# harp_rfid_reader.net
KiCad netlist of a schematic drawn in EAGLE
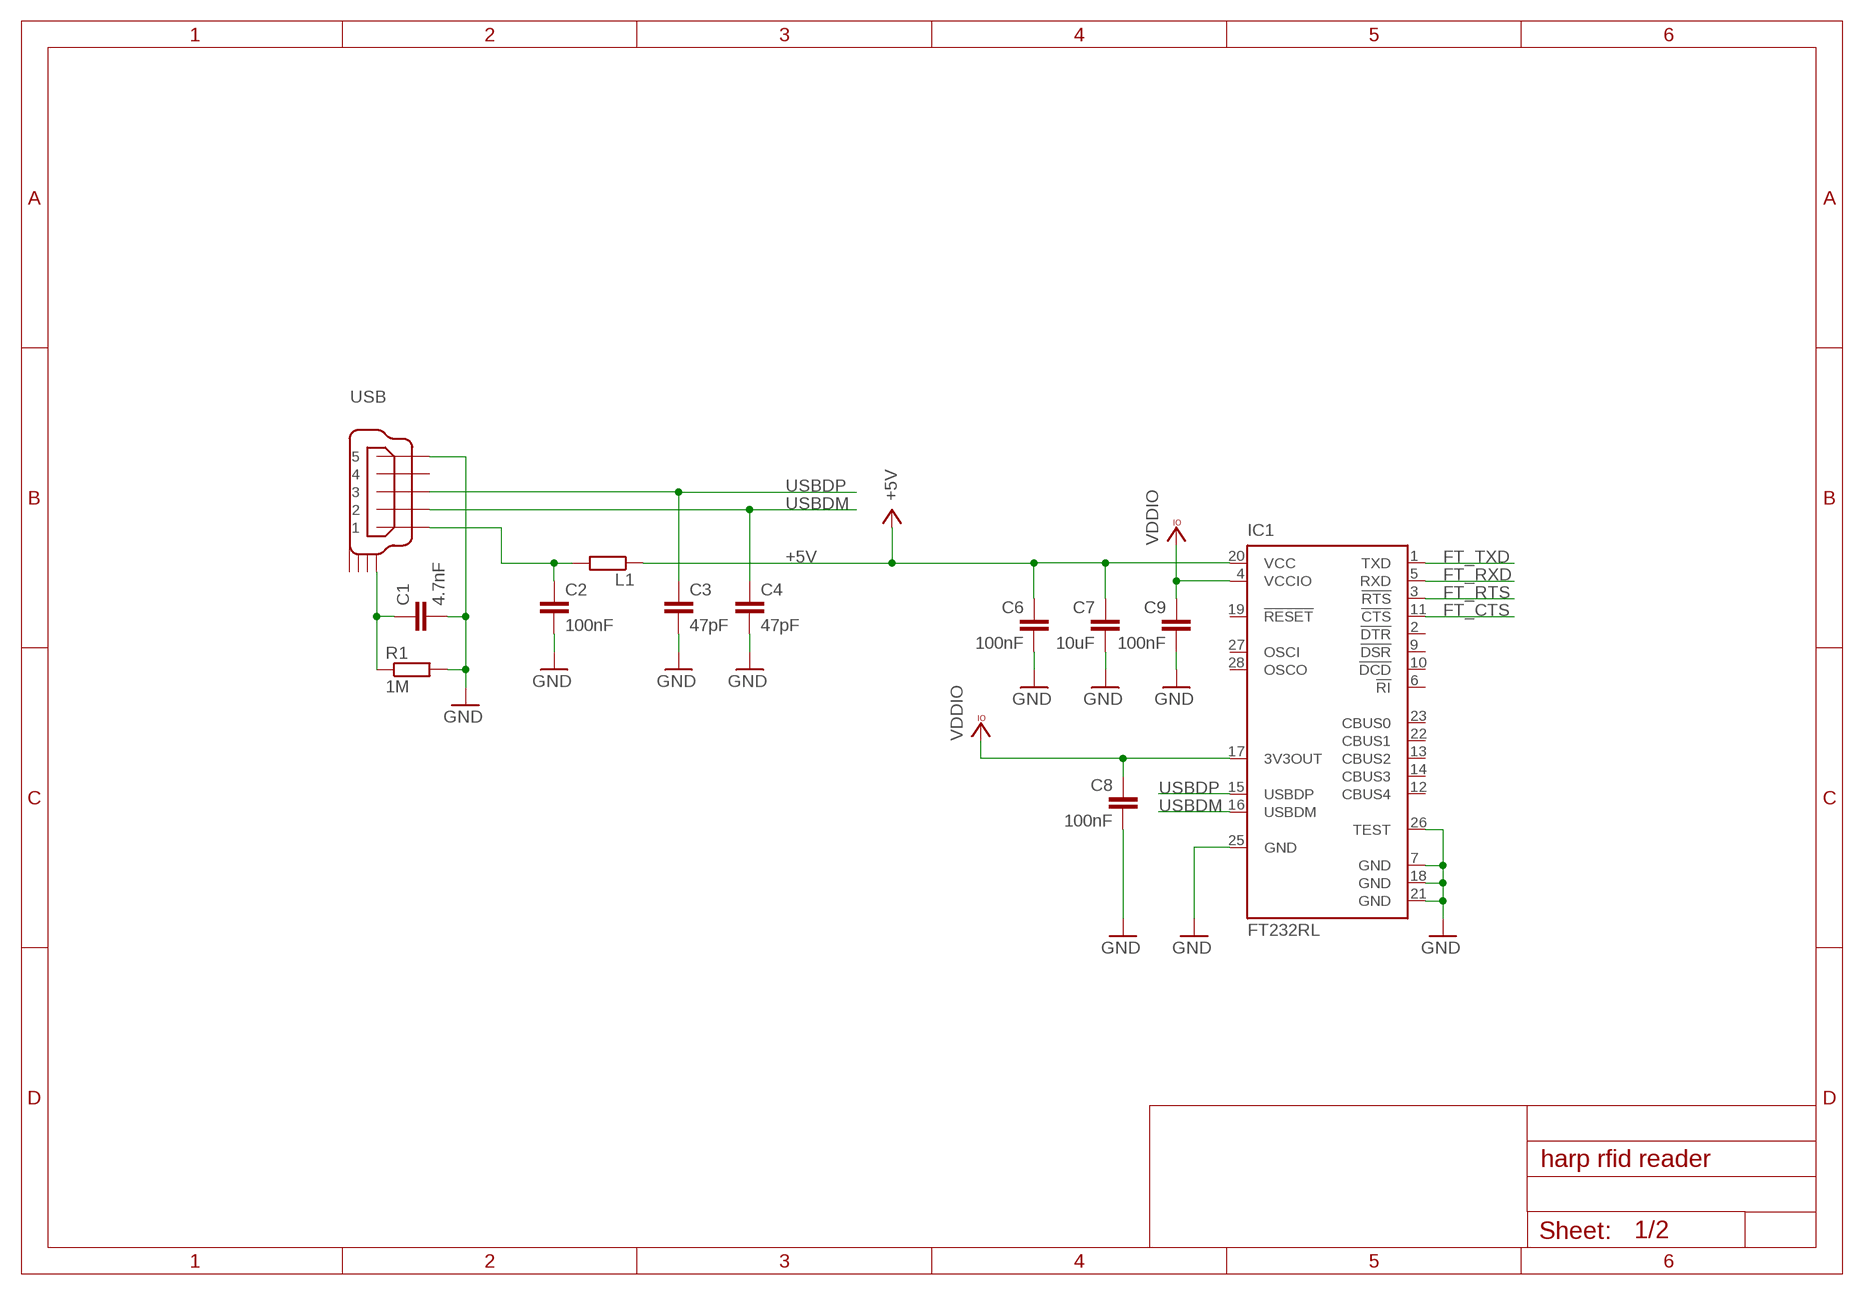
[diagram p0: schematic, sheet 1]
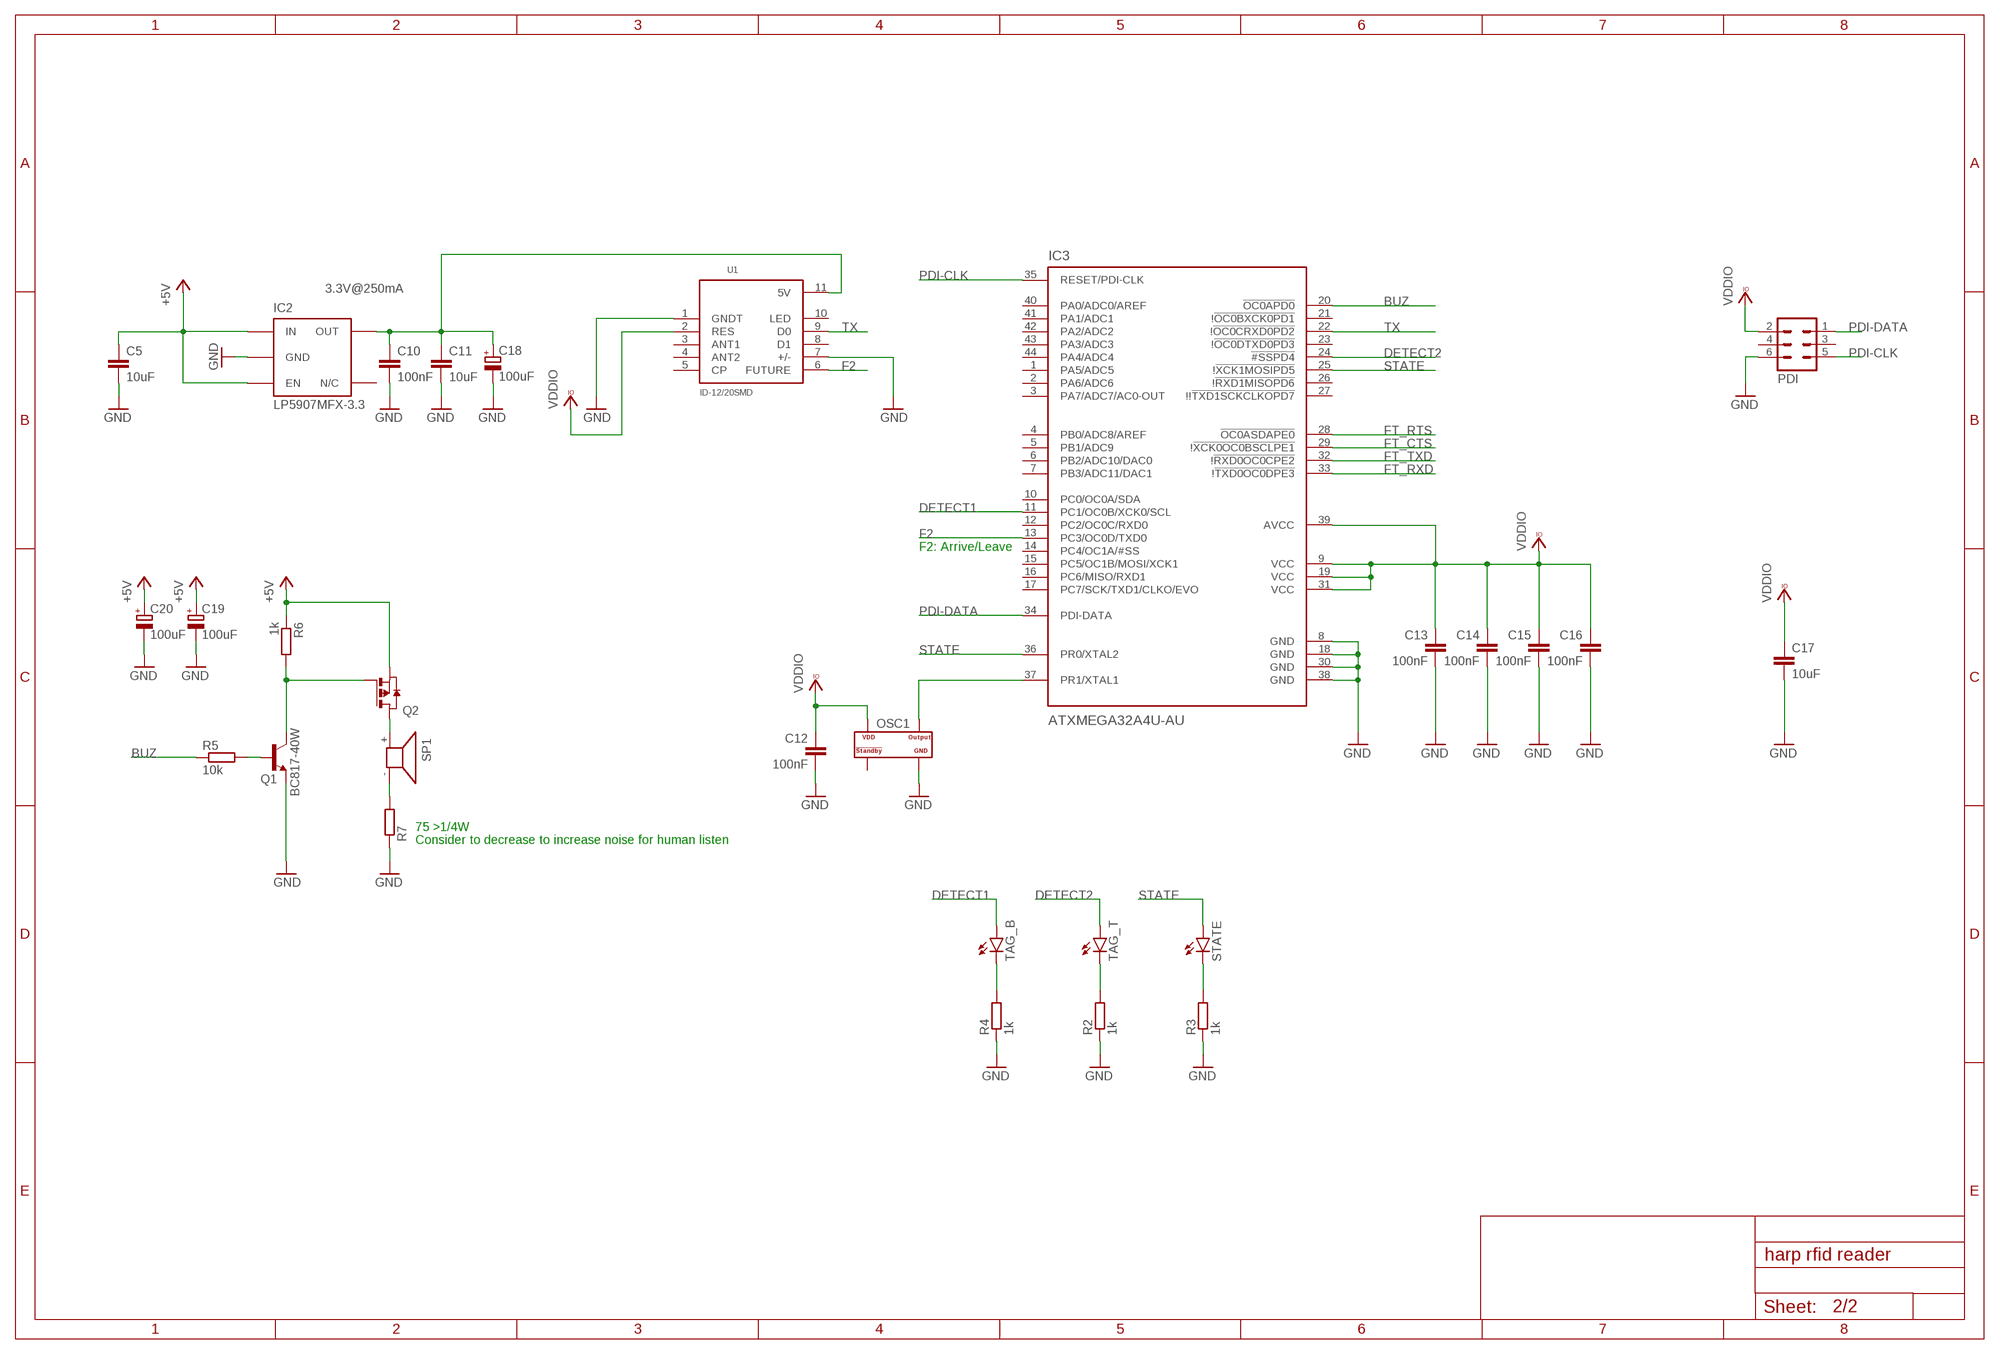
[diagram p1: schematic, sheet 2]

(export (version "E")
  (design (tool "Eeschema 10.0.6"))
  (components
    (comp (ref "C1")
      (value "4.7nF")
      (footprint "eagle-import:C0402")
      (libsource (lib "eagle-import") (part "C-EUC0402"))
    )
    (comp (ref "C2")
      (value "100nF")
      (footprint "eagle-import:C0402")
      (libsource (lib "eagle-import") (part "C-EUC0402"))
    )
    (comp (ref "C3")
      (value "47pF")
      (footprint "eagle-import:C0402")
      (libsource (lib "eagle-import") (part "C-EUC0402"))
    )
    (comp (ref "C4")
      (value "47pF")
      (footprint "eagle-import:C0402")
      (libsource (lib "eagle-import") (part "C-EUC0402"))
    )
    (comp (ref "C6")
      (value "100nF")
      (footprint "eagle-import:C0402")
      (libsource (lib "eagle-import") (part "C-EUC0402"))
    )
    (comp (ref "C7")
      (value "10uF")
      (footprint "eagle-import:C0603")
      (libsource (lib "eagle-import") (part "C-EUC0603"))
    )
    (comp (ref "C8")
      (value "100nF")
      (footprint "eagle-import:C0402")
      (libsource (lib "eagle-import") (part "C-EUC0402"))
    )
    (comp (ref "C9")
      (value "100nF")
      (footprint "eagle-import:C0402")
      (libsource (lib "eagle-import") (part "C-EUC0402"))
    )
    (comp (ref "IC1")
      (value "FT232RL")
      (footprint "eagle-import:SSOP28")
      (libsource (lib "eagle-import") (part "FT232RL"))
    )
    (comp (ref "L1")
      (value "???")
      (footprint "eagle-import:R0805")
      (libsource (lib "eagle-import") (part "R-EU_R0805"))
    )
    (comp (ref "R1")
      (value "1M")
      (footprint "eagle-import:R0402")
      (libsource (lib "eagle-import") (part "R-EU_R0402"))
    )
    (comp (ref "USB")
      (value "USB_MINI_B")
      (footprint "eagle-import:240-0002-1")
      (libsource (lib "eagle-import") (part "USB_MINI_B"))
    )
    (comp (ref "C5")
      (value "10uF")
      (footprint "eagle-import:C0603")
      (libsource (lib "eagle-import") (part "C-EUC0603"))
    )
    (comp (ref "C10")
      (value "100nF")
      (footprint "eagle-import:C0402")
      (libsource (lib "eagle-import") (part "C-EUC0402"))
    )
    (comp (ref "C11")
      (value "10uF")
      (footprint "eagle-import:C0603")
      (libsource (lib "eagle-import") (part "C-EUC0603"))
    )
    (comp (ref "C12")
      (value "100nF")
      (footprint "eagle-import:C0402")
      (libsource (lib "eagle-import") (part "C-EUC0402"))
    )
    (comp (ref "C13")
      (value "100nF")
      (footprint "eagle-import:C0402")
      (libsource (lib "eagle-import") (part "C-EUC0402"))
    )
    (comp (ref "C14")
      (value "100nF")
      (footprint "eagle-import:C0402")
      (libsource (lib "eagle-import") (part "C-EUC0402"))
    )
    (comp (ref "C15")
      (value "100nF")
      (footprint "eagle-import:C0402")
      (libsource (lib "eagle-import") (part "C-EUC0402"))
    )
    (comp (ref "C16")
      (value "100nF")
      (footprint "eagle-import:C0402")
      (libsource (lib "eagle-import") (part "C-EUC0402"))
    )
    (comp (ref "C17")
      (value "10uF")
      (footprint "eagle-import:C0603")
      (libsource (lib "eagle-import") (part "C-EUC0603"))
    )
    (comp (ref "C18")
      (value "100uF")
      (footprint "eagle-import:CT3216")
      (libsource (lib "eagle-import") (part "CPOL-EUCT3216"))
    )
    (comp (ref "C19")
      (value "100uF")
      (footprint "eagle-import:CT3216")
      (libsource (lib "eagle-import") (part "CPOL-EUCT3216"))
    )
    (comp (ref "C20")
      (value "100uF")
      (footprint "eagle-import:CT3216")
      (libsource (lib "eagle-import") (part "CPOL-EUCT3216"))
    )
    (comp (ref "IC2")
      (value "LP5907MFX-3.3")
      (footprint "eagle-import:TSOT23-5")
      (libsource (lib "eagle-import") (part "TLV700XX"))
    )
    (comp (ref "IC3")
      (value "ATXMEGA32A4U-AU")
      (footprint "eagle-import:QFP80P1200X1200X120-44N")
      (libsource (lib "eagle-import") (part "AT-XMEGA-XXA4-AU"))
    )
    (comp (ref "OSC1")
      (value "CNP-MISCELLANEOUS_OSCILLATOR")
      (footprint "eagle-import:CNP-MISCELLANEOUS_OSCILLATOR_3.2X2.5")
      (libsource (lib "eagle-import") (part "CNP-MISCELLANEOUS_OSCILLATOR"))
    )
    (comp (ref "PDI")
      (value "MA03-2")
      (footprint "eagle-import:MA03-2")
      (libsource (lib "eagle-import") (part "MA03-2"))
    )
    (comp (ref "Q1")
      (value "BC817-40W")
      (footprint "eagle-import:SOT323-BEC")
      (libsource (lib "eagle-import") (part "BC817"))
    )
    (comp (ref "Q2")
      (value "PMOSSOT223")
      (footprint "eagle-import:SOT223")
      (libsource (lib "eagle-import") (part "PMOSSOT223"))
    )
    (comp (ref "R2")
      (value "1k")
      (footprint "eagle-import:R0402")
      (libsource (lib "eagle-import") (part "rcl_334_R-EU_R0402"))
    )
    (comp (ref "R3")
      (value "1k")
      (footprint "eagle-import:R0402")
      (libsource (lib "eagle-import") (part "rcl_334_R-EU_R0402"))
    )
    (comp (ref "R4")
      (value "1k")
      (footprint "eagle-import:R0402")
      (libsource (lib "eagle-import") (part "rcl_334_R-EU_R0402"))
    )
    (comp (ref "R5")
      (value "10k")
      (footprint "eagle-import:R0402")
      (libsource (lib "eagle-import") (part "R-EU_R0402"))
    )
    (comp (ref "R6")
      (value "1k")
      (footprint "eagle-import:R0402")
      (libsource (lib "eagle-import") (part "R-EU_R0402"))
    )
    (comp (ref "R7")
      (value "75 >1/4W")
      (footprint "eagle-import:R0402")
      (libsource (lib "eagle-import") (part "R-EU_R0402"))
    )
    (comp (ref "SP1")
      (value "BUZZER-COIL_SMT-0540-S-R")
      (footprint "eagle-import:BUZZER-COIL_SMT-0540-S-R")
      (libsource (lib "eagle-import") (part "BUZZER-COIL_SMT-0540-S-R"))
    )
    (comp (ref "STATE")
      (value "LEDCHIP-LED0603")
      (footprint "eagle-import:CHIP-LED0603")
      (libsource (lib "eagle-import") (part "LEDCHIP-LED0603"))
    )
    (comp (ref "TAG_B")
      (value "LEDCHIP-LED0603")
      (footprint "eagle-import:CHIP-LED0603")
      (libsource (lib "eagle-import") (part "LEDCHIP-LED0603"))
    )
    (comp (ref "TAG_T")
      (value "LEDCHIP-LED0603")
      (footprint "eagle-import:CHIP-LED0603")
      (libsource (lib "eagle-import") (part "LEDCHIP-LED0603"))
    )
    (comp (ref "U1")
      (value "ID-12/20SMD")
      (footprint "eagle-import:ID-12_SMD")
      (libsource (lib "eagle-import") (part "ID-12/20SMD"))
    )
  )
  (nets
    (net (code "1") (name "+5V") (class "Default")
      (node (ref "C19") (pin "+") (pinfunction "+_+") (pintype "passive"))
      (node (ref "C20") (pin "+") (pinfunction "+_+") (pintype "passive"))
      (node (ref "C5") (pin "1") (pinfunction "1_1") (pintype "passive"))
      (node (ref "C6") (pin "1") (pinfunction "1_1") (pintype "passive"))
      (node (ref "C7") (pin "1") (pinfunction "1_1") (pintype "passive"))
      (node (ref "IC1") (pin "20") (pinfunction "VCC_20") (pintype "power_in"))
      (node (ref "IC2") (pin "1") (pinfunction "IN_1") (pintype "bidirectional"))
      (node (ref "IC2") (pin "3") (pinfunction "EN_3") (pintype "bidirectional"))
      (node (ref "L1") (pin "1") (pinfunction "1_1") (pintype "passive"))
      (node (ref "Q2") (pin "3") (pinfunction "S_3") (pintype "passive"))
      (node (ref "R6") (pin "1") (pinfunction "1_1") (pintype "passive"))
    )
    (net (code "2") (name "BUZ") (class "Default")
      (node (ref "IC3") (pin "20") (pinfunction "~{OC0APD0}_20") (pintype "bidirectional"))
      (node (ref "R5") (pin "1") (pinfunction "1_1") (pintype "passive"))
    )
    (net (code "3") (name "DETECT1") (class "Default")
      (node (ref "IC3") (pin "11") (pinfunction "PC1/OC0B/XCK0/SCL_11") (pintype "bidirectional"))
      (node (ref "TAG_B") (pin "A") (pinfunction "A_A") (pintype "passive"))
    )
    (net (code "4") (name "DETECT2") (class "Default")
      (node (ref "IC3") (pin "24") (pinfunction "~{#SSPD4}_24") (pintype "bidirectional"))
      (node (ref "TAG_T") (pin "A") (pinfunction "A_A") (pintype "passive"))
    )
    (net (code "5") (name "F2") (class "Default")
      (node (ref "IC3") (pin "13") (pinfunction "PC3/OC0D/TXD0_13") (pintype "bidirectional"))
      (node (ref "U1") (pin "6") (pinfunction "FUTURE_6") (pintype "bidirectional"))
    )
    (net (code "6") (name "FT_CTS") (class "Default")
      (node (ref "IC1") (pin "11") (pinfunction "~{CTS}_11") (pintype "input"))
      (node (ref "IC3") (pin "29") (pinfunction "~XCK0OC0BSCLPE1_29") (pintype "bidirectional"))
    )
    (net (code "7") (name "FT_RTS") (class "Default")
      (node (ref "IC1") (pin "3") (pinfunction "~{RTS}_3") (pintype "output"))
      (node (ref "IC3") (pin "28") (pinfunction "~{OC0ASDAPE0}_28") (pintype "bidirectional"))
    )
    (net (code "8") (name "FT_RXD") (class "Default")
      (node (ref "IC1") (pin "5") (pinfunction "RXD_5") (pintype "input"))
      (node (ref "IC3") (pin "33") (pinfunction "~TXD0OC0DPE3_33") (pintype "bidirectional"))
    )
    (net (code "9") (name "FT_TXD") (class "Default")
      (node (ref "IC1") (pin "1") (pinfunction "TXD_1") (pintype "output"))
      (node (ref "IC3") (pin "32") (pinfunction "~RXD0OC0CPE2_32") (pintype "bidirectional"))
    )
    (net (code "10") (name "GND") (class "Default")
      (node (ref "C1") (pin "2") (pinfunction "2_2") (pintype "passive"))
      (node (ref "C10") (pin "2") (pinfunction "2_2") (pintype "passive"))
      (node (ref "C11") (pin "2") (pinfunction "2_2") (pintype "passive"))
      (node (ref "C12") (pin "2") (pinfunction "2_2") (pintype "passive"))
      (node (ref "C13") (pin "2") (pinfunction "2_2") (pintype "passive"))
      (node (ref "C14") (pin "2") (pinfunction "2_2") (pintype "passive"))
      (node (ref "C15") (pin "2") (pinfunction "2_2") (pintype "passive"))
      (node (ref "C16") (pin "2") (pinfunction "2_2") (pintype "passive"))
      (node (ref "C17") (pin "2") (pinfunction "2_2") (pintype "passive"))
      (node (ref "C18") (pin "-") (pinfunction "-_-") (pintype "passive"))
      (node (ref "C19") (pin "-") (pinfunction "-_-") (pintype "passive"))
      (node (ref "C2") (pin "2") (pinfunction "2_2") (pintype "passive"))
      (node (ref "C20") (pin "-") (pinfunction "-_-") (pintype "passive"))
      (node (ref "C3") (pin "2") (pinfunction "2_2") (pintype "passive"))
      (node (ref "C4") (pin "2") (pinfunction "2_2") (pintype "passive"))
      (node (ref "C5") (pin "2") (pinfunction "2_2") (pintype "passive"))
      (node (ref "C6") (pin "2") (pinfunction "2_2") (pintype "passive"))
      (node (ref "C7") (pin "2") (pinfunction "2_2") (pintype "passive"))
      (node (ref "C8") (pin "2") (pinfunction "2_2") (pintype "passive"))
      (node (ref "C9") (pin "2") (pinfunction "2_2") (pintype "passive"))
      (node (ref "IC1") (pin "18") (pinfunction "GND_18") (pintype "power_in"))
      (node (ref "IC1") (pin "21") (pinfunction "GND_21") (pintype "power_in"))
      (node (ref "IC1") (pin "25") (pinfunction "GND_25") (pintype "power_in"))
      (node (ref "IC1") (pin "26") (pinfunction "TEST_26") (pintype "input"))
      (node (ref "IC1") (pin "7") (pinfunction "GND_7") (pintype "power_in"))
      (node (ref "IC2") (pin "2") (pinfunction "GND_2") (pintype "bidirectional"))
      (node (ref "IC3") (pin "18") (pinfunction "GND_18") (pintype "power_in"))
      (node (ref "IC3") (pin "30") (pinfunction "GND_30") (pintype "power_in"))
      (node (ref "IC3") (pin "38") (pinfunction "GND_38") (pintype "power_in"))
      (node (ref "IC3") (pin "8") (pinfunction "GND_8") (pintype "power_in"))
      (node (ref "OSC1") (pin "P$2") (pinfunction "GND_P$2") (pintype "passive"))
      (node (ref "PDI") (pin "6") (pinfunction "6_6") (pintype "passive"))
      (node (ref "Q1") (pin "E") (pinfunction "E_E") (pintype "passive"))
      (node (ref "R1") (pin "2") (pinfunction "2_2") (pintype "passive"))
      (node (ref "R2") (pin "1") (pinfunction "1_1") (pintype "passive"))
      (node (ref "R3") (pin "1") (pinfunction "1_1") (pintype "passive"))
      (node (ref "R4") (pin "1") (pinfunction "1_1") (pintype "passive"))
      (node (ref "R7") (pin "1") (pinfunction "1_1") (pintype "passive"))
      (node (ref "U1") (pin "1") (pinfunction "GNDT_1") (pintype "bidirectional"))
      (node (ref "U1") (pin "7") (pinfunction "+/-_7") (pintype "bidirectional"))
      (node (ref "USB") (pin "P$5") (pinfunction "5_P$5") (pintype "bidirectional"))
    )
    (net (code "11") (name "Net-(IC2-OUT)") (class "Default")
      (node (ref "C10") (pin "1") (pinfunction "1_1") (pintype "passive"))
      (node (ref "C11") (pin "1") (pinfunction "1_1") (pintype "passive"))
      (node (ref "C18") (pin "+") (pinfunction "+_+") (pintype "passive"))
      (node (ref "IC2") (pin "5") (pinfunction "OUT_5") (pintype "bidirectional"))
      (node (ref "U1") (pin "11") (pinfunction "5V_11") (pintype "bidirectional"))
    )
    (net (code "12") (name "Net-(IC3-PR1{slash}XTAL1)") (class "Default")
      (node (ref "IC3") (pin "37") (pinfunction "PR1/XTAL1_37") (pintype "bidirectional"))
      (node (ref "OSC1") (pin "P$3") (pinfunction "OUTPUT_P$3") (pintype "passive"))
    )
    (net (code "13") (name "Net-(Q1-PadB)") (class "Default")
      (node (ref "Q1") (pin "B") (pinfunction "B_B") (pintype "passive"))
      (node (ref "R5") (pin "2") (pinfunction "2_2") (pintype "passive"))
    )
    (net (code "14") (name "Net-(Q2-D-Pad2)") (class "Default")
      (node (ref "Q2") (pin "2") (pinfunction "D_2") (pintype "passive"))
      (node (ref "Q2") (pin "4") (pinfunction "D_4") (pintype "passive"))
      (node (ref "SP1") (pin "+") (pinfunction "+_+") (pintype "passive"))
    )
    (net (code "15") (name "Net-(Q2-G)") (class "Default")
      (node (ref "Q1") (pin "C") (pinfunction "C_C") (pintype "passive"))
      (node (ref "Q2") (pin "1") (pinfunction "G_1") (pintype "passive"))
      (node (ref "R6") (pin "2") (pinfunction "2_2") (pintype "passive"))
    )
    (net (code "16") (name "Net-(R2-Pad2)") (class "Default")
      (node (ref "R2") (pin "2") (pinfunction "2_2") (pintype "passive"))
      (node (ref "TAG_T") (pin "C") (pinfunction "C_C") (pintype "passive"))
    )
    (net (code "17") (name "Net-(R3-Pad2)") (class "Default")
      (node (ref "R3") (pin "2") (pinfunction "2_2") (pintype "passive"))
      (node (ref "STATE") (pin "C") (pinfunction "C_C") (pintype "passive"))
    )
    (net (code "18") (name "Net-(R4-Pad2)") (class "Default")
      (node (ref "R4") (pin "2") (pinfunction "2_2") (pintype "passive"))
      (node (ref "TAG_B") (pin "C") (pinfunction "C_C") (pintype "passive"))
    )
    (net (code "19") (name "Net-(R7-Pad2)") (class "Default")
      (node (ref "R7") (pin "2") (pinfunction "2_2") (pintype "passive"))
      (node (ref "SP1") (pin "-") (pinfunction "-_-") (pintype "passive"))
    )
    (net (code "20") (name "Net-(USB-1)") (class "Default")
      (node (ref "C2") (pin "1") (pinfunction "1_1") (pintype "passive"))
      (node (ref "L1") (pin "2") (pinfunction "2_2") (pintype "passive"))
      (node (ref "USB") (pin "P$1") (pinfunction "1_P$1") (pintype "bidirectional"))
    )
    (net (code "21") (name "Net-(USB-P$1)") (class "Default")
      (node (ref "C1") (pin "1") (pinfunction "1_1") (pintype "passive"))
      (node (ref "R1") (pin "1") (pinfunction "1_1") (pintype "passive"))
      (node (ref "USB") (pin "SHIELD_1") (pinfunction "P$1_SHIELD_1") (pintype "bidirectional"))
    )
    (net (code "22") (name "PDI-CLK") (class "Default")
      (node (ref "IC3") (pin "35") (pinfunction "RESET/PDI-CLK_35") (pintype "input"))
      (node (ref "PDI") (pin "5") (pinfunction "5_5") (pintype "passive"))
    )
    (net (code "23") (name "PDI-DATA") (class "Default")
      (node (ref "IC3") (pin "34") (pinfunction "PDI-DATA_34") (pintype "bidirectional"))
      (node (ref "PDI") (pin "1") (pinfunction "1_1") (pintype "passive"))
    )
    (net (code "24") (name "STATE") (class "Default")
      (node (ref "IC3") (pin "25") (pinfunction "~XCK1MOSIPD5_25") (pintype "bidirectional"))
      (node (ref "IC3") (pin "36") (pinfunction "PR0/XTAL2_36") (pintype "bidirectional"))
      (node (ref "STATE") (pin "A") (pinfunction "A_A") (pintype "passive"))
    )
    (net (code "25") (name "TX") (class "Default")
      (node (ref "IC3") (pin "22") (pinfunction "~OC0CRXD0PD2_22") (pintype "bidirectional"))
      (node (ref "U1") (pin "9") (pinfunction "D0_9") (pintype "bidirectional"))
    )
    (net (code "26") (name "USBDM") (class "Default")
      (node (ref "C4") (pin "1") (pinfunction "1_1") (pintype "passive"))
      (node (ref "IC1") (pin "16") (pinfunction "USBDM_16") (pintype "bidirectional"))
      (node (ref "USB") (pin "P$2") (pinfunction "2_P$2") (pintype "bidirectional"))
    )
    (net (code "27") (name "USBDP") (class "Default")
      (node (ref "C3") (pin "1") (pinfunction "1_1") (pintype "passive"))
      (node (ref "IC1") (pin "15") (pinfunction "USBDP_15") (pintype "bidirectional"))
      (node (ref "USB") (pin "P$3") (pinfunction "3_P$3") (pintype "bidirectional"))
    )
    (net (code "28") (name "VCCIO") (class "Default")
      (node (ref "C12") (pin "1") (pinfunction "1_1") (pintype "passive"))
      (node (ref "C13") (pin "1") (pinfunction "1_1") (pintype "passive"))
      (node (ref "C14") (pin "1") (pinfunction "1_1") (pintype "passive"))
      (node (ref "C15") (pin "1") (pinfunction "1_1") (pintype "passive"))
      (node (ref "C16") (pin "1") (pinfunction "1_1") (pintype "passive"))
      (node (ref "C17") (pin "1") (pinfunction "1_1") (pintype "passive"))
      (node (ref "C8") (pin "1") (pinfunction "1_1") (pintype "passive"))
      (node (ref "C9") (pin "1") (pinfunction "1_1") (pintype "passive"))
      (node (ref "IC1") (pin "17") (pinfunction "3V3OUT_17") (pintype "output"))
      (node (ref "IC1") (pin "4") (pinfunction "VCCIO_4") (pintype "power_in"))
      (node (ref "IC3") (pin "19") (pinfunction "VCC_19") (pintype "power_in"))
      (node (ref "IC3") (pin "31") (pinfunction "VCC_31") (pintype "power_in"))
      (node (ref "IC3") (pin "39") (pinfunction "AVCC_39") (pintype "power_in"))
      (node (ref "IC3") (pin "9") (pinfunction "VCC_9") (pintype "power_in"))
      (node (ref "OSC1") (pin "P$4") (pinfunction "VDD_P$4") (pintype "passive"))
      (node (ref "PDI") (pin "2") (pinfunction "2_2") (pintype "passive"))
      (node (ref "U1") (pin "2") (pinfunction "RES_2") (pintype "bidirectional"))
    )
    (net (code "29") (name "unconnected-(IC1-CBUS0-Pad23)") (class "Default")
      (node (ref "IC1") (pin "23") (pinfunction "CBUS0_23") (pintype "bidirectional"))
    )
    (net (code "30") (name "unconnected-(IC1-CBUS1-Pad22)") (class "Default")
      (node (ref "IC1") (pin "22") (pinfunction "CBUS1_22") (pintype "bidirectional"))
    )
    (net (code "31") (name "unconnected-(IC1-CBUS2-Pad13)") (class "Default")
      (node (ref "IC1") (pin "13") (pinfunction "CBUS2_13") (pintype "bidirectional"))
    )
    (net (code "32") (name "unconnected-(IC1-CBUS3-Pad14)") (class "Default")
      (node (ref "IC1") (pin "14") (pinfunction "CBUS3_14") (pintype "bidirectional"))
    )
    (net (code "33") (name "unconnected-(IC1-CBUS4-Pad12)") (class "Default")
      (node (ref "IC1") (pin "12") (pinfunction "CBUS4_12") (pintype "bidirectional"))
    )
    (net (code "34") (name "unconnected-(IC1-OSCI-Pad27)") (class "Default")
      (node (ref "IC1") (pin "27") (pinfunction "OSCI_27") (pintype "input"))
    )
    (net (code "35") (name "unconnected-(IC1-OSCO-Pad28)") (class "Default")
      (node (ref "IC1") (pin "28") (pinfunction "OSCO_28") (pintype "output"))
    )
    (net (code "36") (name "unconnected-(IC1-~{DCD}-Pad10)") (class "Default")
      (node (ref "IC1") (pin "10") (pinfunction "~{DCD}_10") (pintype "input"))
    )
    (net (code "37") (name "unconnected-(IC1-~{DSR}-Pad9)") (class "Default")
      (node (ref "IC1") (pin "9") (pinfunction "~{DSR}_9") (pintype "input"))
    )
    (net (code "38") (name "unconnected-(IC1-~{DTR}-Pad2)") (class "Default")
      (node (ref "IC1") (pin "2") (pinfunction "~{DTR}_2") (pintype "output"))
    )
    (net (code "39") (name "unconnected-(IC1-~{RESET}-Pad19)") (class "Default")
      (node (ref "IC1") (pin "19") (pinfunction "~{RESET}_19") (pintype "input"))
    )
    (net (code "40") (name "unconnected-(IC1-~{RI}-Pad6)") (class "Default")
      (node (ref "IC1") (pin "6") (pinfunction "~{RI}_6") (pintype "input"))
    )
    (net (code "41") (name "unconnected-(IC2-N{slash}C-Pad4)") (class "Default")
      (node (ref "IC2") (pin "4") (pinfunction "N/C_4") (pintype "bidirectional"))
    )
    (net (code "42") (name "unconnected-(IC3-PA0{slash}ADC0{slash}AREF-Pad40)") (class "Default")
      (node (ref "IC3") (pin "40") (pinfunction "PA0/ADC0/AREF_40") (pintype "bidirectional"))
    )
    (net (code "43") (name "unconnected-(IC3-PA1{slash}ADC1-Pad41)") (class "Default")
      (node (ref "IC3") (pin "41") (pinfunction "PA1/ADC1_41") (pintype "bidirectional"))
    )
    (net (code "44") (name "unconnected-(IC3-PA2{slash}ADC2-Pad42)") (class "Default")
      (node (ref "IC3") (pin "42") (pinfunction "PA2/ADC2_42") (pintype "bidirectional"))
    )
    (net (code "45") (name "unconnected-(IC3-PA3{slash}ADC3-Pad43)") (class "Default")
      (node (ref "IC3") (pin "43") (pinfunction "PA3/ADC3_43") (pintype "bidirectional"))
    )
    (net (code "46") (name "unconnected-(IC3-PA4{slash}ADC4-Pad44)") (class "Default")
      (node (ref "IC3") (pin "44") (pinfunction "PA4/ADC4_44") (pintype "bidirectional"))
    )
    (net (code "47") (name "unconnected-(IC3-PA5{slash}ADC5-Pad1)") (class "Default")
      (node (ref "IC3") (pin "1") (pinfunction "PA5/ADC5_1") (pintype "bidirectional"))
    )
    (net (code "48") (name "unconnected-(IC3-PA6{slash}ADC6-Pad2)") (class "Default")
      (node (ref "IC3") (pin "2") (pinfunction "PA6/ADC6_2") (pintype "bidirectional"))
    )
    (net (code "49") (name "unconnected-(IC3-PA7{slash}ADC7{slash}AC0-OUT-Pad3)") (class "Default")
      (node (ref "IC3") (pin "3") (pinfunction "PA7/ADC7/AC0-OUT_3") (pintype "bidirectional"))
    )
    (net (code "50") (name "unconnected-(IC3-PB0{slash}ADC8{slash}AREF-Pad4)") (class "Default")
      (node (ref "IC3") (pin "4") (pinfunction "PB0/ADC8/AREF_4") (pintype "bidirectional"))
    )
    (net (code "51") (name "unconnected-(IC3-PB1{slash}ADC9-Pad5)") (class "Default")
      (node (ref "IC3") (pin "5") (pinfunction "PB1/ADC9_5") (pintype "bidirectional"))
    )
    (net (code "52") (name "unconnected-(IC3-PB2{slash}ADC10{slash}DAC0-Pad6)") (class "Default")
      (node (ref "IC3") (pin "6") (pinfunction "PB2/ADC10/DAC0_6") (pintype "bidirectional"))
    )
    (net (code "53") (name "unconnected-(IC3-PB3{slash}ADC11{slash}DAC1-Pad7)") (class "Default")
      (node (ref "IC3") (pin "7") (pinfunction "PB3/ADC11/DAC1_7") (pintype "bidirectional"))
    )
    (net (code "54") (name "unconnected-(IC3-PC0{slash}OC0A{slash}SDA-Pad10)") (class "Default")
      (node (ref "IC3") (pin "10") (pinfunction "PC0/OC0A/SDA_10") (pintype "bidirectional"))
    )
    (net (code "55") (name "unconnected-(IC3-PC2{slash}OC0C{slash}RXD0-Pad12)") (class "Default")
      (node (ref "IC3") (pin "12") (pinfunction "PC2/OC0C/RXD0_12") (pintype "bidirectional"))
    )
    (net (code "56") (name "unconnected-(IC3-PC4{slash}OC1A{slash}#SS-Pad14)") (class "Default")
      (node (ref "IC3") (pin "14") (pinfunction "PC4/OC1A/#SS_14") (pintype "bidirectional"))
    )
    (net (code "57") (name "unconnected-(IC3-PC5{slash}OC1B{slash}MOSI{slash}XCK1-Pad15)") (class "Default")
      (node (ref "IC3") (pin "15") (pinfunction "PC5/OC1B/MOSI/XCK1_15") (pintype "bidirectional"))
    )
    (net (code "58") (name "unconnected-(IC3-PC6{slash}MISO{slash}RXD1-Pad16)") (class "Default")
      (node (ref "IC3") (pin "16") (pinfunction "PC6/MISO/RXD1_16") (pintype "bidirectional"))
    )
    (net (code "59") (name "unconnected-(IC3-PC7{slash}SCK{slash}TXD1{slash}CLKO{slash}EVO-Pad17)") (class "Default")
      (node (ref "IC3") (pin "17") (pinfunction "PC7/SCK/TXD1/CLKO/EVO_17") (pintype "bidirectional"))
    )
    (net (code "60") (name "unconnected-(IC3-~OC0BXCK0PD1-Pad21)") (class "Default")
      (node (ref "IC3") (pin "21") (pinfunction "~OC0BXCK0PD1_21") (pintype "bidirectional"))
    )
    (net (code "61") (name "unconnected-(IC3-~OC0DTXD0PD3-Pad23)") (class "Default")
      (node (ref "IC3") (pin "23") (pinfunction "~OC0DTXD0PD3_23") (pintype "bidirectional"))
    )
    (net (code "62") (name "unconnected-(IC3-~RXD1MISOPD6-Pad26)") (class "Default")
      (node (ref "IC3") (pin "26") (pinfunction "~RXD1MISOPD6_26") (pintype "bidirectional"))
    )
    (net (code "63") (name "unconnected-(IC3-~~{TXD1SCKCLKOPD7}-Pad27)") (class "Default")
      (node (ref "IC3") (pin "27") (pinfunction "~~{TXD1SCKCLKOPD7}_27") (pintype "bidirectional"))
    )
    (net (code "64") (name "unconnected-(OSC1-STANDBY#-PadP$1)") (class "Default")
      (node (ref "OSC1") (pin "P$1") (pinfunction "STANDBY#_P$1") (pintype "passive"))
    )
    (net (code "65") (name "unconnected-(PDI-Pad3)") (class "Default")
      (node (ref "PDI") (pin "3") (pinfunction "3_3") (pintype "passive"))
    )
    (net (code "66") (name "unconnected-(PDI-Pad4)") (class "Default")
      (node (ref "PDI") (pin "4") (pinfunction "4_4") (pintype "passive"))
    )
    (net (code "67") (name "unconnected-(U1-ANT1-Pad3)") (class "Default")
      (node (ref "U1") (pin "3") (pinfunction "ANT1_3") (pintype "bidirectional"))
    )
    (net (code "68") (name "unconnected-(U1-ANT2-Pad4)") (class "Default")
      (node (ref "U1") (pin "4") (pinfunction "ANT2_4") (pintype "bidirectional"))
    )
    (net (code "69") (name "unconnected-(U1-CP-Pad5)") (class "Default")
      (node (ref "U1") (pin "5") (pinfunction "CP_5") (pintype "bidirectional"))
    )
    (net (code "70") (name "unconnected-(U1-D1-Pad8)") (class "Default")
      (node (ref "U1") (pin "8") (pinfunction "D1_8") (pintype "bidirectional"))
    )
    (net (code "71") (name "unconnected-(U1-LED-Pad10)") (class "Default")
      (node (ref "U1") (pin "10") (pinfunction "LED_10") (pintype "bidirectional"))
    )
    (net (code "72") (name "unconnected-(USB-4-PadP$4)") (class "Default")
      (node (ref "USB") (pin "P$4") (pinfunction "4_P$4") (pintype "bidirectional"))
    )
    (net (code "73") (name "unconnected-(USB-P$2-PadSHIELD_2)") (class "Default")
      (node (ref "USB") (pin "SHIELD_2") (pinfunction "P$2_SHIELD_2") (pintype "bidirectional"))
    )
    (net (code "74") (name "unconnected-(USB-P$3-PadSHIELD_3)") (class "Default")
      (node (ref "USB") (pin "SHIELD_3") (pinfunction "P$3_SHIELD_3") (pintype "bidirectional"))
    )
    (net (code "75") (name "unconnected-(USB-P$4-PadSHIELD_4)") (class "Default")
      (node (ref "USB") (pin "SHIELD_4") (pinfunction "P$4_SHIELD_4") (pintype "bidirectional"))
    )
  )
)
